# ECG-BioZ-Holter.net
KiCad netlist of a schematic drawn in EAGLE
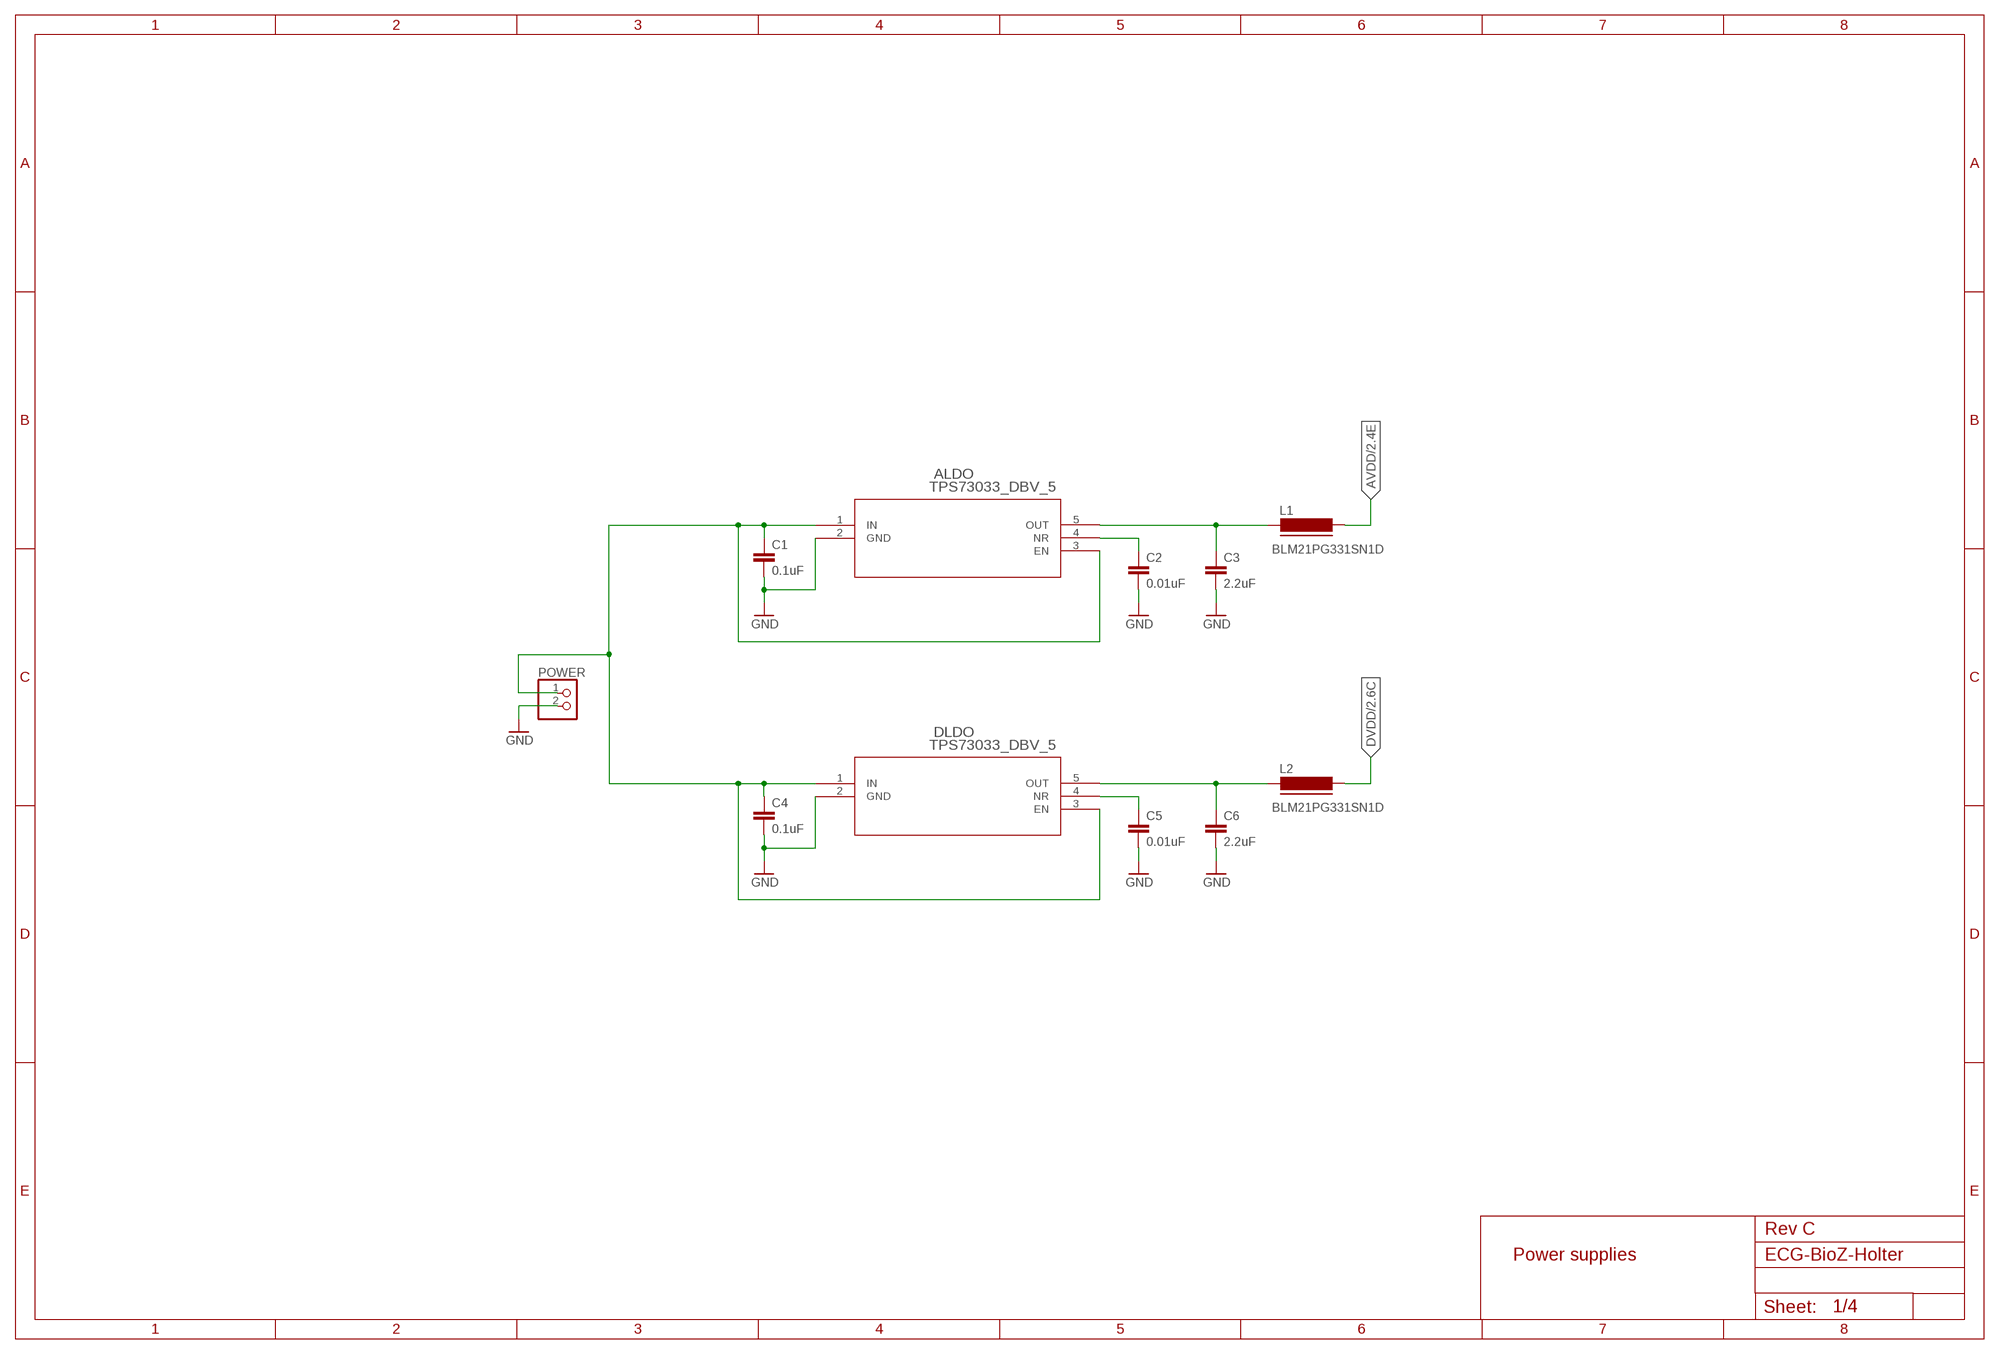
[diagram p0: schematic, sheet 1]
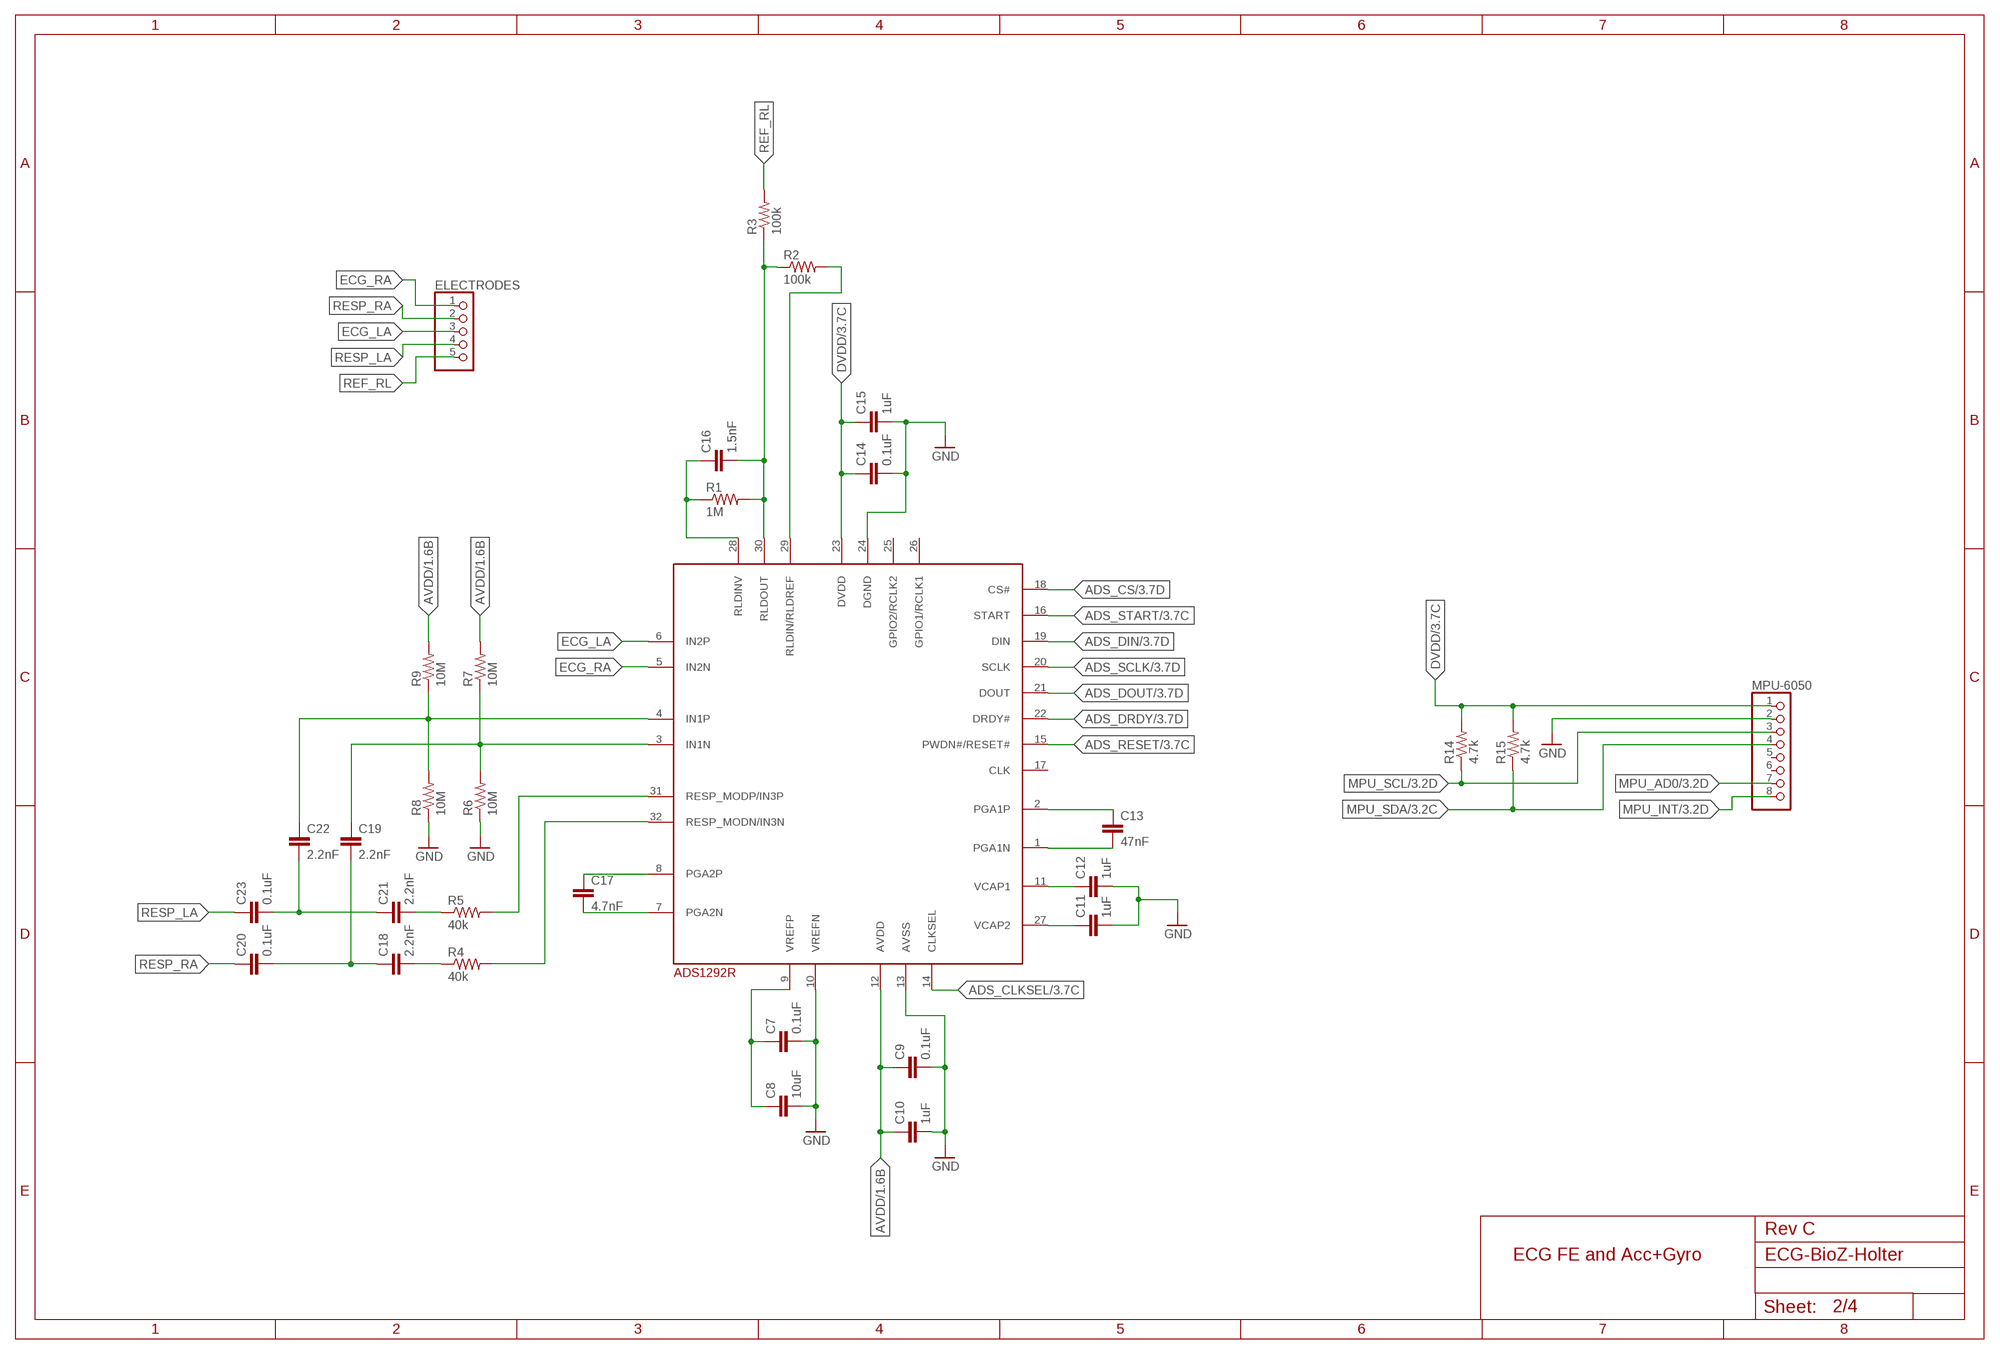
[diagram p1: schematic, sheet 2]
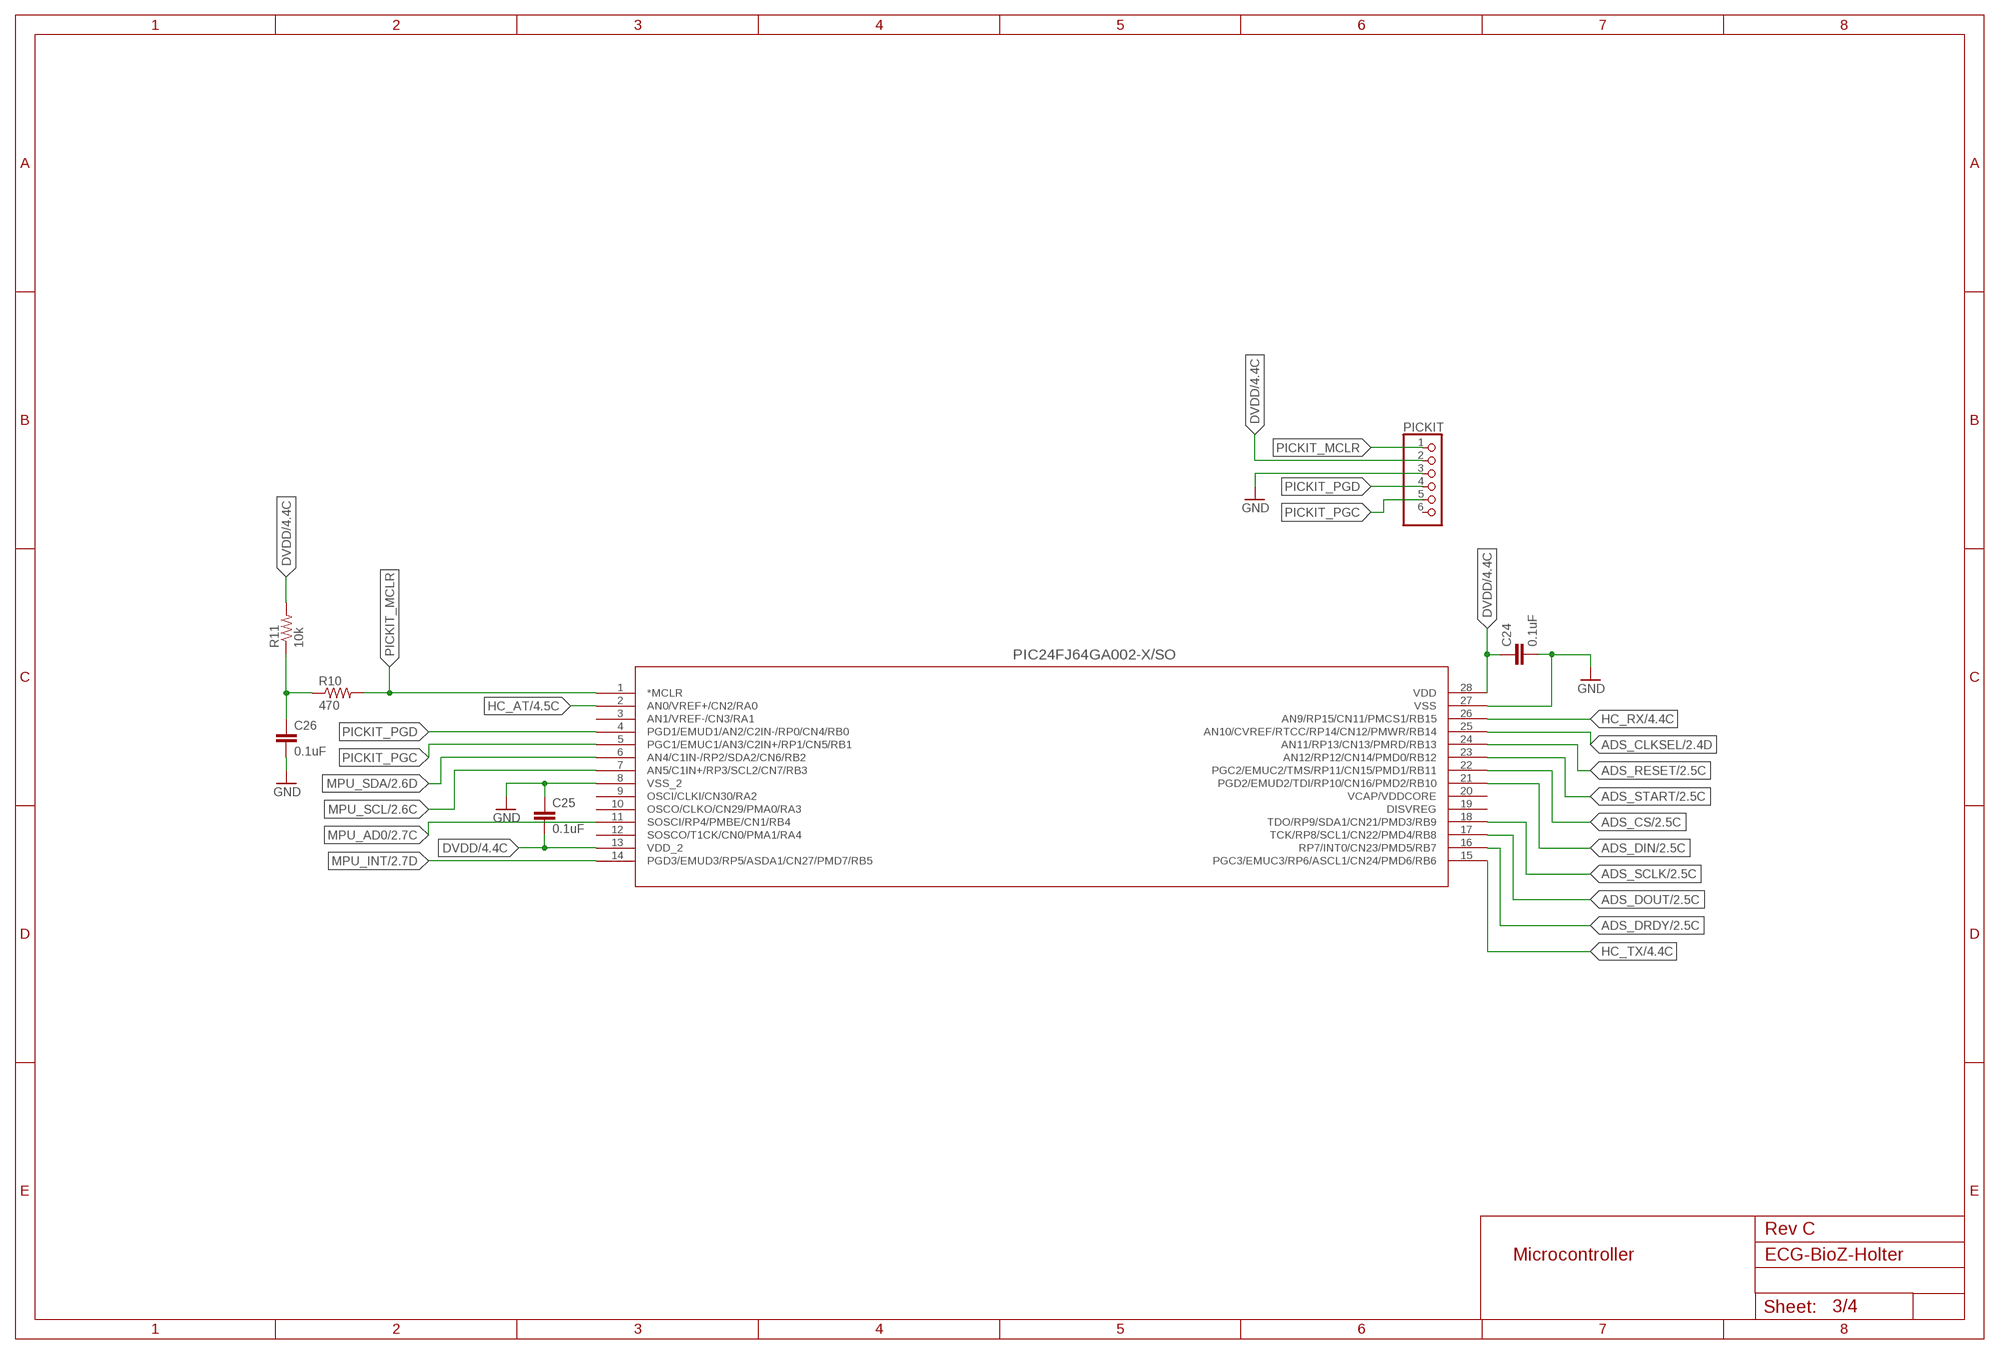
[diagram p2: schematic, sheet 3]
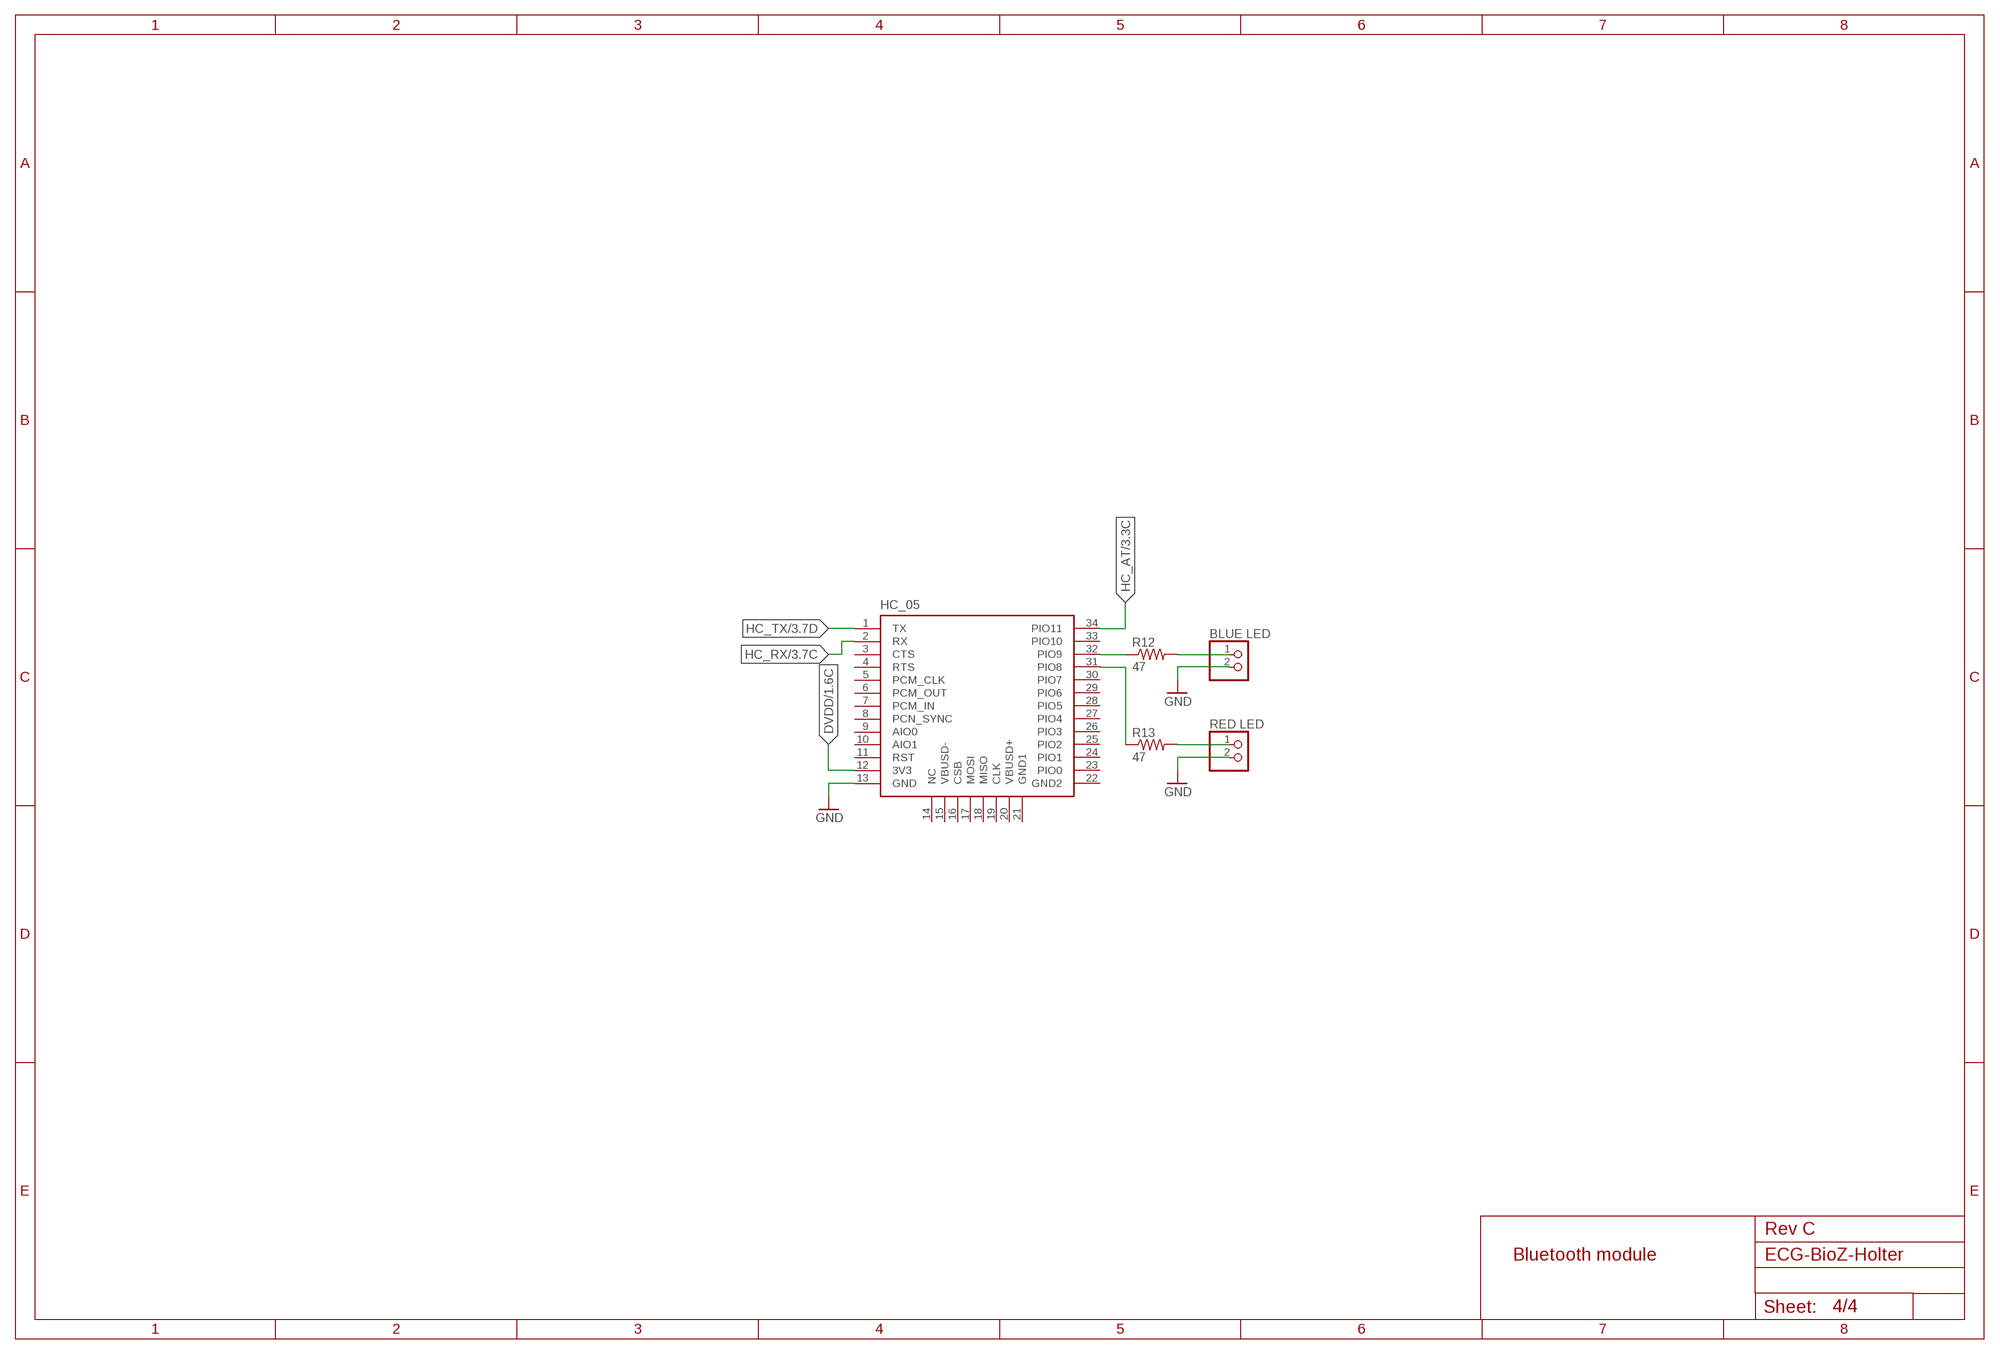
[diagram p3: schematic, sheet 4]

(export (version "E")
  (design (tool "Eeschema 10.0.6"))
  (components
    (comp (ref "ALDO")
      (value "TPS73033_DBV_5")
      (footprint "eagle-import:DBV5")
      (fields
        (field (name "GENERIC_PART_NUMBER") "TPS73033")
        (field (name "MANUFACTURER") "Texas Instruments")
        (field (name "MANUFACTURER_PART_NUMBER") "tps73033_dbv_5")
      )
      (libsource (lib "eagle-import") (part "TPS73033_DBV_5"))
    )
    (comp (ref "C1")
      (value "0.1uF")
      (footprint "eagle-import:C0805")
      (libsource (lib "eagle-import") (part "C-EUC0805"))
    )
    (comp (ref "C2")
      (value "0.01uF")
      (footprint "eagle-import:C0805")
      (libsource (lib "eagle-import") (part "C-EUC0805"))
    )
    (comp (ref "C3")
      (value "2.2uF")
      (footprint "eagle-import:C0805")
      (libsource (lib "eagle-import") (part "C-EUC0805"))
    )
    (comp (ref "C4")
      (value "0.1uF")
      (footprint "eagle-import:C0805")
      (libsource (lib "eagle-import") (part "C-EUC0805"))
    )
    (comp (ref "C5")
      (value "0.01uF")
      (footprint "eagle-import:C0805")
      (libsource (lib "eagle-import") (part "C-EUC0805"))
    )
    (comp (ref "C6")
      (value "2.2uF")
      (footprint "eagle-import:C0805")
      (libsource (lib "eagle-import") (part "C-EUC0805"))
    )
    (comp (ref "DLDO")
      (value "TPS73033_DBV_5")
      (footprint "eagle-import:DBV5")
      (fields
        (field (name "GENERIC_PART_NUMBER") "TPS73033")
        (field (name "MANUFACTURER") "Texas Instruments")
        (field (name "MANUFACTURER_PART_NUMBER") "tps73033_dbv_5")
      )
      (libsource (lib "eagle-import") (part "TPS73033_DBV_5"))
    )
    (comp (ref "L1")
      (value "BLM21PG331SN1D")
      (footprint "eagle-import:FB805")
      (libsource (lib "eagle-import") (part "FERRITE-0805"))
    )
    (comp (ref "L2")
      (value "BLM21PG331SN1D")
      (footprint "eagle-import:FB805")
      (libsource (lib "eagle-import") (part "FERRITE-0805"))
    )
    (comp (ref "POWER")
      (value "PINHD-1X2")
      (footprint "eagle-import:1X02")
      (libsource (lib "eagle-import") (part "PINHD-1X2"))
    )
    (comp (ref "C24")
      (value "0.1uF")
      (footprint "eagle-import:C0805")
      (libsource (lib "eagle-import") (part "C-EUC0805"))
    )
    (comp (ref "C25")
      (value "0.1uF")
      (footprint "eagle-import:C0805")
      (libsource (lib "eagle-import") (part "C-EUC0805"))
    )
    (comp (ref "C26")
      (value "0.1uF")
      (footprint "eagle-import:C0805")
      (libsource (lib "eagle-import") (part "C-EUC0805"))
    )
    (comp (ref "PIC24F")
      (value "PIC24FJ64GA002-X/SO")
      (footprint "eagle-import:SOIC28-W_MC")
      (libsource (lib "eagle-import") (part "PIC24FJ64GA002-X/SO"))
    )
    (comp (ref "PICKIT")
      (value "PINHD-1X6")
      (footprint "eagle-import:1X06")
      (libsource (lib "eagle-import") (part "PINHD-1X6"))
    )
    (comp (ref "R10")
      (value "470")
      (footprint "eagle-import:R0805")
      (libsource (lib "eagle-import") (part "R-US_R0805"))
    )
    (comp (ref "R11")
      (value "10k")
      (footprint "eagle-import:R0805")
      (libsource (lib "eagle-import") (part "R-US_R0805"))
    )
    (comp (ref "ADS1292R")
      (value "ADS1292R")
      (footprint "eagle-import:TQFP-32")
      (libsource (lib "eagle-import") (part "ADS1292R"))
    )
    (comp (ref "C7")
      (value "0.1uF")
      (footprint "eagle-import:C0805")
      (libsource (lib "eagle-import") (part "C-EUC0805"))
    )
    (comp (ref "C8")
      (value "10uF")
      (footprint "eagle-import:C0805")
      (libsource (lib "eagle-import") (part "C-EUC0805"))
    )
    (comp (ref "C9")
      (value "0.1uF")
      (footprint "eagle-import:C0805")
      (libsource (lib "eagle-import") (part "C-EUC0805"))
    )
    (comp (ref "C10")
      (value "1uF")
      (footprint "eagle-import:C0805")
      (libsource (lib "eagle-import") (part "C-EUC0805"))
    )
    (comp (ref "C11")
      (value "1uF")
      (footprint "eagle-import:C0805")
      (libsource (lib "eagle-import") (part "C-EUC0805"))
    )
    (comp (ref "C12")
      (value "1uF")
      (footprint "eagle-import:C0805")
      (libsource (lib "eagle-import") (part "C-EUC0805"))
    )
    (comp (ref "C13")
      (value "47nF")
      (footprint "eagle-import:C0805")
      (libsource (lib "eagle-import") (part "C-EUC0805"))
    )
    (comp (ref "C14")
      (value "0.1uF")
      (footprint "eagle-import:C0805")
      (libsource (lib "eagle-import") (part "C-EUC0805"))
    )
    (comp (ref "C15")
      (value "1uF")
      (footprint "eagle-import:C0805")
      (libsource (lib "eagle-import") (part "C-EUC0805"))
    )
    (comp (ref "C16")
      (value "1.5nF")
      (footprint "eagle-import:C0805")
      (libsource (lib "eagle-import") (part "C-EUC0805"))
    )
    (comp (ref "C17")
      (value "4.7nF")
      (footprint "eagle-import:C0805")
      (libsource (lib "eagle-import") (part "C-EUC0805"))
    )
    (comp (ref "C18")
      (value "2.2nF")
      (footprint "eagle-import:C0805")
      (libsource (lib "eagle-import") (part "C-EUC0805"))
    )
    (comp (ref "C19")
      (value "2.2nF")
      (footprint "eagle-import:C0805")
      (libsource (lib "eagle-import") (part "C-EUC0805"))
    )
    (comp (ref "C20")
      (value "0.1uF")
      (footprint "eagle-import:C0805")
      (libsource (lib "eagle-import") (part "C-EUC0805"))
    )
    (comp (ref "C21")
      (value "2.2nF")
      (footprint "eagle-import:C0805")
      (libsource (lib "eagle-import") (part "C-EUC0805"))
    )
    (comp (ref "C22")
      (value "2.2nF")
      (footprint "eagle-import:C0805")
      (libsource (lib "eagle-import") (part "C-EUC0805"))
    )
    (comp (ref "C23")
      (value "0.1uF")
      (footprint "eagle-import:C0805")
      (libsource (lib "eagle-import") (part "C-EUC0805"))
    )
    (comp (ref "ELECTRODES")
      (value "PINHD-1X5")
      (footprint "eagle-import:1X05")
      (libsource (lib "eagle-import") (part "PINHD-1X5"))
    )
    (comp (ref "MPU")
      (value "MPU-6050")
      (footprint "eagle-import:1X08")
      (libsource (lib "eagle-import") (part "PINHD-1X8"))
    )
    (comp (ref "R1")
      (value "1M")
      (footprint "eagle-import:R0805")
      (libsource (lib "eagle-import") (part "R-US_R0805"))
    )
    (comp (ref "R2")
      (value "100k")
      (footprint "eagle-import:R0805")
      (libsource (lib "eagle-import") (part "R-US_R0805"))
    )
    (comp (ref "R3")
      (value "100k")
      (footprint "eagle-import:R0805")
      (libsource (lib "eagle-import") (part "R-US_R0805"))
    )
    (comp (ref "R4")
      (value "40k")
      (footprint "eagle-import:R0805")
      (libsource (lib "eagle-import") (part "R-US_R0805"))
    )
    (comp (ref "R5")
      (value "40k")
      (footprint "eagle-import:R0805")
      (libsource (lib "eagle-import") (part "R-US_R0805"))
    )
    (comp (ref "R6")
      (value "10M")
      (footprint "eagle-import:R0805")
      (libsource (lib "eagle-import") (part "R-US_R0805"))
    )
    (comp (ref "R7")
      (value "10M")
      (footprint "eagle-import:R0805")
      (libsource (lib "eagle-import") (part "R-US_R0805"))
    )
    (comp (ref "R8")
      (value "10M")
      (footprint "eagle-import:R0805")
      (libsource (lib "eagle-import") (part "R-US_R0805"))
    )
    (comp (ref "R9")
      (value "10M")
      (footprint "eagle-import:R0805")
      (libsource (lib "eagle-import") (part "R-US_R0805"))
    )
    (comp (ref "R14")
      (value "4.7k")
      (footprint "eagle-import:R0805")
      (libsource (lib "eagle-import") (part "R-US_R0805"))
    )
    (comp (ref "R15")
      (value "4.7k")
      (footprint "eagle-import:R0805")
      (libsource (lib "eagle-import") (part "R-US_R0805"))
    )
    (comp (ref "BLUE")
      (value "BLUE LED")
      (footprint "eagle-import:1X02")
      (libsource (lib "eagle-import") (part "PINHD-1X2"))
    )
    (comp (ref "HC_05")
      (value "HC_05")
      (footprint "eagle-import:BLUETOOTH_SMD")
      (libsource (lib "eagle-import") (part "HC_05"))
    )
    (comp (ref "R12")
      (value "47")
      (footprint "eagle-import:R0805")
      (libsource (lib "eagle-import") (part "R-US_R0805"))
    )
    (comp (ref "R13")
      (value "47")
      (footprint "eagle-import:R0805")
      (libsource (lib "eagle-import") (part "R-US_R0805"))
    )
    (comp (ref "RED")
      (value "RED LED")
      (footprint "eagle-import:1X02")
      (libsource (lib "eagle-import") (part "PINHD-1X2"))
    )
  )
  (nets
    (net (code "1") (name "ADS_CLKSEL") (class "Default")
      (node (ref "ADS1292R") (pin "14") (pinfunction "CLKSEL_14") (pintype "bidirectional"))
      (node (ref "PIC24F") (pin "25") (pinfunction "AN10/CVREF/RTCC/RP14/CN12/PMWR/RB14_25") (pintype "passive"))
    )
    (net (code "2") (name "ADS_CS") (class "Default")
      (node (ref "ADS1292R") (pin "18") (pinfunction "CS#_18") (pintype "bidirectional"))
      (node (ref "PIC24F") (pin "22") (pinfunction "PGC2/EMUC2/TMS/RP11/CN15/PMD1/RB11_22") (pintype "passive"))
    )
    (net (code "3") (name "ADS_DIN") (class "Default")
      (node (ref "ADS1292R") (pin "19") (pinfunction "DIN_19") (pintype "bidirectional"))
      (node (ref "PIC24F") (pin "21") (pinfunction "PGD2/EMUD2/TDI/RP10/CN16/PMD2/RB10_21") (pintype "passive"))
    )
    (net (code "4") (name "ADS_DOUT") (class "Default")
      (node (ref "ADS1292R") (pin "21") (pinfunction "DOUT_21") (pintype "bidirectional"))
      (node (ref "PIC24F") (pin "17") (pinfunction "TCK/RP8/SCL1/CN22/PMD4/RB8_17") (pintype "passive"))
    )
    (net (code "5") (name "ADS_DRDY") (class "Default")
      (node (ref "ADS1292R") (pin "22") (pinfunction "DRDY#_22") (pintype "bidirectional"))
      (node (ref "PIC24F") (pin "16") (pinfunction "RP7/INT0/CN23/PMD5/RB7_16") (pintype "passive"))
    )
    (net (code "6") (name "ADS_RESET") (class "Default")
      (node (ref "ADS1292R") (pin "15") (pinfunction "PWDN#/RESET#_15") (pintype "bidirectional"))
      (node (ref "PIC24F") (pin "24") (pinfunction "AN11/RP13/CN13/PMRD/RB13_24") (pintype "passive"))
    )
    (net (code "7") (name "ADS_SCLK") (class "Default")
      (node (ref "ADS1292R") (pin "20") (pinfunction "SCLK_20") (pintype "bidirectional"))
      (node (ref "PIC24F") (pin "18") (pinfunction "TDO/RP9/SDA1/CN21/PMD3/RB9_18") (pintype "passive"))
    )
    (net (code "8") (name "ADS_START") (class "Default")
      (node (ref "ADS1292R") (pin "16") (pinfunction "START_16") (pintype "bidirectional"))
      (node (ref "PIC24F") (pin "23") (pinfunction "AN12/RP12/CN14/PMD0/RB12_23") (pintype "passive"))
    )
    (net (code "9") (name "AVDD") (class "Default")
      (node (ref "ADS1292R") (pin "12") (pinfunction "AVDD_12") (pintype "bidirectional"))
      (node (ref "C10") (pin "1") (pinfunction "1_1") (pintype "passive"))
      (node (ref "C9") (pin "1") (pinfunction "1_1") (pintype "passive"))
      (node (ref "L1") (pin "2") (pinfunction "2_2") (pintype "passive"))
      (node (ref "R7") (pin "2") (pinfunction "2_2") (pintype "passive"))
      (node (ref "R9") (pin "2") (pinfunction "2_2") (pintype "passive"))
    )
    (net (code "10") (name "DVDD") (class "Default")
      (node (ref "ADS1292R") (pin "23") (pinfunction "DVDD_23") (pintype "bidirectional"))
      (node (ref "C14") (pin "1") (pinfunction "1_1") (pintype "passive"))
      (node (ref "C15") (pin "1") (pinfunction "1_1") (pintype "passive"))
      (node (ref "C24") (pin "1") (pinfunction "1_1") (pintype "passive"))
      (node (ref "C25") (pin "2") (pinfunction "2_2") (pintype "passive"))
      (node (ref "HC_05") (pin "12") (pinfunction "3V3_12") (pintype "bidirectional"))
      (node (ref "L2") (pin "2") (pinfunction "2_2") (pintype "passive"))
      (node (ref "MPU") (pin "1") (pinfunction "1_1") (pintype "passive"))
      (node (ref "PIC24F") (pin "13") (pinfunction "VDD_2_13") (pintype "passive"))
      (node (ref "PIC24F") (pin "28") (pinfunction "VDD_28") (pintype "passive"))
      (node (ref "PICKIT") (pin "2") (pinfunction "2_2") (pintype "passive"))
      (node (ref "R11") (pin "2") (pinfunction "2_2") (pintype "passive"))
      (node (ref "R14") (pin "2") (pinfunction "2_2") (pintype "passive"))
      (node (ref "R15") (pin "2") (pinfunction "2_2") (pintype "passive"))
    )
    (net (code "11") (name "ECG_LA") (class "Default")
      (node (ref "ADS1292R") (pin "6") (pinfunction "IN2P_6") (pintype "bidirectional"))
      (node (ref "ELECTRODES") (pin "3") (pinfunction "3_3") (pintype "passive"))
    )
    (net (code "12") (name "ECG_RA") (class "Default")
      (node (ref "ADS1292R") (pin "5") (pinfunction "IN2N_5") (pintype "bidirectional"))
      (node (ref "ELECTRODES") (pin "1") (pinfunction "1_1") (pintype "passive"))
    )
    (net (code "13") (name "GND") (class "Default")
      (node (ref "ADS1292R") (pin "10") (pinfunction "VREFN_10") (pintype "bidirectional"))
      (node (ref "ADS1292R") (pin "13") (pinfunction "AVSS_13") (pintype "bidirectional"))
      (node (ref "ADS1292R") (pin "24") (pinfunction "DGND_24") (pintype "bidirectional"))
      (node (ref "ALDO") (pin "2") (pinfunction "GND_2") (pintype "power_in"))
      (node (ref "BLUE") (pin "2") (pinfunction "2_2") (pintype "passive"))
      (node (ref "C1") (pin "2") (pinfunction "2_2") (pintype "passive"))
      (node (ref "C10") (pin "2") (pinfunction "2_2") (pintype "passive"))
      (node (ref "C11") (pin "2") (pinfunction "2_2") (pintype "passive"))
      (node (ref "C12") (pin "2") (pinfunction "2_2") (pintype "passive"))
      (node (ref "C14") (pin "2") (pinfunction "2_2") (pintype "passive"))
      (node (ref "C15") (pin "2") (pinfunction "2_2") (pintype "passive"))
      (node (ref "C2") (pin "2") (pinfunction "2_2") (pintype "passive"))
      (node (ref "C24") (pin "2") (pinfunction "2_2") (pintype "passive"))
      (node (ref "C25") (pin "1") (pinfunction "1_1") (pintype "passive"))
      (node (ref "C26") (pin "2") (pinfunction "2_2") (pintype "passive"))
      (node (ref "C3") (pin "2") (pinfunction "2_2") (pintype "passive"))
      (node (ref "C4") (pin "2") (pinfunction "2_2") (pintype "passive"))
      (node (ref "C5") (pin "2") (pinfunction "2_2") (pintype "passive"))
      (node (ref "C6") (pin "2") (pinfunction "2_2") (pintype "passive"))
      (node (ref "C7") (pin "2") (pinfunction "2_2") (pintype "passive"))
      (node (ref "C8") (pin "2") (pinfunction "2_2") (pintype "passive"))
      (node (ref "C9") (pin "2") (pinfunction "2_2") (pintype "passive"))
      (node (ref "DLDO") (pin "2") (pinfunction "GND_2") (pintype "power_in"))
      (node (ref "HC_05") (pin "13") (pinfunction "GND_13") (pintype "bidirectional"))
      (node (ref "MPU") (pin "2") (pinfunction "2_2") (pintype "passive"))
      (node (ref "PIC24F") (pin "27") (pinfunction "VSS_27") (pintype "passive"))
      (node (ref "PIC24F") (pin "8") (pinfunction "VSS_2_8") (pintype "passive"))
      (node (ref "PICKIT") (pin "3") (pinfunction "3_3") (pintype "passive"))
      (node (ref "POWER") (pin "2") (pinfunction "2_2") (pintype "passive"))
      (node (ref "R6") (pin "1") (pinfunction "1_1") (pintype "passive"))
      (node (ref "R8") (pin "1") (pinfunction "1_1") (pintype "passive"))
      (node (ref "RED") (pin "2") (pinfunction "2_2") (pintype "passive"))
    )
    (net (code "14") (name "HC_AT") (class "Default")
      (node (ref "HC_05") (pin "34") (pinfunction "PIO11_34") (pintype "bidirectional"))
      (node (ref "PIC24F") (pin "2") (pinfunction "AN0/VREF+/CN2/RA0_2") (pintype "passive"))
    )
    (net (code "15") (name "HC_RX") (class "Default")
      (node (ref "HC_05") (pin "2") (pinfunction "RX_2") (pintype "bidirectional"))
      (node (ref "PIC24F") (pin "26") (pinfunction "AN9/RP15/CN11/PMCS1/RB15_26") (pintype "passive"))
    )
    (net (code "16") (name "HC_TX") (class "Default")
      (node (ref "HC_05") (pin "1") (pinfunction "TX_1") (pintype "bidirectional"))
      (node (ref "PIC24F") (pin "15") (pinfunction "PGC3/EMUC3/RP6/ASCL1/CN24/PMD6/RB6_15") (pintype "passive"))
    )
    (net (code "17") (name "MPU_AD0") (class "Default")
      (node (ref "MPU") (pin "7") (pinfunction "7_7") (pintype "passive"))
      (node (ref "PIC24F") (pin "11") (pinfunction "SOSCI/RP4/PMBE/CN1/RB4_11") (pintype "passive"))
    )
    (net (code "18") (name "MPU_INT") (class "Default")
      (node (ref "MPU") (pin "8") (pinfunction "8_8") (pintype "passive"))
      (node (ref "PIC24F") (pin "14") (pinfunction "PGD3/EMUD3/RP5/ASDA1/CN27/PMD7/RB5_14") (pintype "passive"))
    )
    (net (code "19") (name "MPU_SCL") (class "Default")
      (node (ref "MPU") (pin "3") (pinfunction "3_3") (pintype "passive"))
      (node (ref "PIC24F") (pin "7") (pinfunction "AN5/C1IN+/RP3/SCL2/CN7/RB3_7") (pintype "passive"))
      (node (ref "R14") (pin "1") (pinfunction "1_1") (pintype "passive"))
    )
    (net (code "20") (name "MPU_SDA") (class "Default")
      (node (ref "MPU") (pin "4") (pinfunction "4_4") (pintype "passive"))
      (node (ref "PIC24F") (pin "6") (pinfunction "AN4/C1IN-/RP2/SDA2/CN6/RB2_6") (pintype "passive"))
      (node (ref "R15") (pin "1") (pinfunction "1_1") (pintype "passive"))
    )
    (net (code "21") (name "Net-(ADS1292R-IN1N)") (class "Default")
      (node (ref "ADS1292R") (pin "3") (pinfunction "IN1N_3") (pintype "bidirectional"))
      (node (ref "C19") (pin "1") (pinfunction "1_1") (pintype "passive"))
      (node (ref "R6") (pin "2") (pinfunction "2_2") (pintype "passive"))
      (node (ref "R7") (pin "1") (pinfunction "1_1") (pintype "passive"))
    )
    (net (code "22") (name "Net-(ADS1292R-IN1P)") (class "Default")
      (node (ref "ADS1292R") (pin "4") (pinfunction "IN1P_4") (pintype "bidirectional"))
      (node (ref "C22") (pin "1") (pinfunction "1_1") (pintype "passive"))
      (node (ref "R8") (pin "2") (pinfunction "2_2") (pintype "passive"))
      (node (ref "R9") (pin "1") (pinfunction "1_1") (pintype "passive"))
    )
    (net (code "23") (name "Net-(ADS1292R-PGA1N)") (class "Default")
      (node (ref "ADS1292R") (pin "1") (pinfunction "PGA1N_1") (pintype "bidirectional"))
      (node (ref "C13") (pin "2") (pinfunction "2_2") (pintype "passive"))
    )
    (net (code "24") (name "Net-(ADS1292R-PGA1P)") (class "Default")
      (node (ref "ADS1292R") (pin "2") (pinfunction "PGA1P_2") (pintype "bidirectional"))
      (node (ref "C13") (pin "1") (pinfunction "1_1") (pintype "passive"))
    )
    (net (code "25") (name "Net-(ADS1292R-PGA2N)") (class "Default")
      (node (ref "ADS1292R") (pin "7") (pinfunction "PGA2N_7") (pintype "bidirectional"))
      (node (ref "C17") (pin "2") (pinfunction "2_2") (pintype "passive"))
    )
    (net (code "26") (name "Net-(ADS1292R-PGA2P)") (class "Default")
      (node (ref "ADS1292R") (pin "8") (pinfunction "PGA2P_8") (pintype "bidirectional"))
      (node (ref "C17") (pin "1") (pinfunction "1_1") (pintype "passive"))
    )
    (net (code "27") (name "Net-(ADS1292R-RESP_MODN{slash}IN3N)") (class "Default")
      (node (ref "ADS1292R") (pin "32") (pinfunction "RESP_MODN/IN3N_32") (pintype "bidirectional"))
      (node (ref "R4") (pin "2") (pinfunction "2_2") (pintype "passive"))
    )
    (net (code "28") (name "Net-(ADS1292R-RESP_MODP{slash}IN3P)") (class "Default")
      (node (ref "ADS1292R") (pin "31") (pinfunction "RESP_MODP/IN3P_31") (pintype "bidirectional"))
      (node (ref "R5") (pin "2") (pinfunction "2_2") (pintype "passive"))
    )
    (net (code "29") (name "Net-(ADS1292R-RLDINV)") (class "Default")
      (node (ref "ADS1292R") (pin "28") (pinfunction "RLDINV_28") (pintype "bidirectional"))
      (node (ref "C16") (pin "1") (pinfunction "1_1") (pintype "passive"))
      (node (ref "R1") (pin "1") (pinfunction "1_1") (pintype "passive"))
    )
    (net (code "30") (name "Net-(ADS1292R-RLDIN{slash}RLDREF)") (class "Default")
      (node (ref "ADS1292R") (pin "29") (pinfunction "RLDIN/RLDREF_29") (pintype "bidirectional"))
      (node (ref "R2") (pin "2") (pinfunction "2_2") (pintype "passive"))
    )
    (net (code "31") (name "Net-(ADS1292R-RLDOUT)") (class "Default")
      (node (ref "ADS1292R") (pin "30") (pinfunction "RLDOUT_30") (pintype "bidirectional"))
      (node (ref "C16") (pin "2") (pinfunction "2_2") (pintype "passive"))
      (node (ref "R1") (pin "2") (pinfunction "2_2") (pintype "passive"))
      (node (ref "R2") (pin "1") (pinfunction "1_1") (pintype "passive"))
      (node (ref "R3") (pin "1") (pinfunction "1_1") (pintype "passive"))
    )
    (net (code "32") (name "Net-(ADS1292R-VCAP1)") (class "Default")
      (node (ref "ADS1292R") (pin "11") (pinfunction "VCAP1_11") (pintype "bidirectional"))
      (node (ref "C12") (pin "1") (pinfunction "1_1") (pintype "passive"))
    )
    (net (code "33") (name "Net-(ADS1292R-VCAP2)") (class "Default")
      (node (ref "ADS1292R") (pin "27") (pinfunction "VCAP2_27") (pintype "bidirectional"))
      (node (ref "C11") (pin "1") (pinfunction "1_1") (pintype "passive"))
    )
    (net (code "34") (name "Net-(ADS1292R-VREFP)") (class "Default")
      (node (ref "ADS1292R") (pin "9") (pinfunction "VREFP_9") (pintype "bidirectional"))
      (node (ref "C7") (pin "1") (pinfunction "1_1") (pintype "passive"))
      (node (ref "C8") (pin "1") (pinfunction "1_1") (pintype "passive"))
    )
    (net (code "35") (name "Net-(ALDO-EN)") (class "Default")
      (node (ref "ALDO") (pin "1") (pinfunction "IN_1") (pintype "input"))
      (node (ref "ALDO") (pin "3") (pinfunction "EN_3") (pintype "passive"))
      (node (ref "C1") (pin "1") (pinfunction "1_1") (pintype "passive"))
      (node (ref "C4") (pin "1") (pinfunction "1_1") (pintype "passive"))
      (node (ref "DLDO") (pin "1") (pinfunction "IN_1") (pintype "input"))
      (node (ref "DLDO") (pin "3") (pinfunction "EN_3") (pintype "passive"))
      (node (ref "POWER") (pin "1") (pinfunction "1_1") (pintype "passive"))
    )
    (net (code "36") (name "Net-(ALDO-NR)") (class "Default")
      (node (ref "ALDO") (pin "4") (pinfunction "NR_4") (pintype "passive"))
      (node (ref "C2") (pin "1") (pinfunction "1_1") (pintype "passive"))
    )
    (net (code "37") (name "Net-(ALDO-OUT)") (class "Default")
      (node (ref "ALDO") (pin "5") (pinfunction "OUT_5") (pintype "output"))
      (node (ref "C3") (pin "1") (pinfunction "1_1") (pintype "passive"))
      (node (ref "L1") (pin "1") (pinfunction "1_1") (pintype "passive"))
    )
    (net (code "38") (name "Net-(BLUE-Pad1)") (class "Default")
      (node (ref "BLUE") (pin "1") (pinfunction "1_1") (pintype "passive"))
      (node (ref "R12") (pin "2") (pinfunction "2_2") (pintype "passive"))
    )
    (net (code "39") (name "Net-(C18-Pad1)") (class "Default")
      (node (ref "C18") (pin "1") (pinfunction "1_1") (pintype "passive"))
      (node (ref "C19") (pin "2") (pinfunction "2_2") (pintype "passive"))
      (node (ref "C20") (pin "2") (pinfunction "2_2") (pintype "passive"))
    )
    (net (code "40") (name "Net-(C18-Pad2)") (class "Default")
      (node (ref "C18") (pin "2") (pinfunction "2_2") (pintype "passive"))
      (node (ref "R4") (pin "1") (pinfunction "1_1") (pintype "passive"))
    )
    (net (code "41") (name "Net-(C21-Pad1)") (class "Default")
      (node (ref "C21") (pin "1") (pinfunction "1_1") (pintype "passive"))
      (node (ref "C22") (pin "2") (pinfunction "2_2") (pintype "passive"))
      (node (ref "C23") (pin "2") (pinfunction "2_2") (pintype "passive"))
    )
    (net (code "42") (name "Net-(C21-Pad2)") (class "Default")
      (node (ref "C21") (pin "2") (pinfunction "2_2") (pintype "passive"))
      (node (ref "R5") (pin "1") (pinfunction "1_1") (pintype "passive"))
    )
    (net (code "43") (name "Net-(C26-Pad1)") (class "Default")
      (node (ref "C26") (pin "1") (pinfunction "1_1") (pintype "passive"))
      (node (ref "R10") (pin "1") (pinfunction "1_1") (pintype "passive"))
      (node (ref "R11") (pin "1") (pinfunction "1_1") (pintype "passive"))
    )
    (net (code "44") (name "Net-(DLDO-NR)") (class "Default")
      (node (ref "C5") (pin "1") (pinfunction "1_1") (pintype "passive"))
      (node (ref "DLDO") (pin "4") (pinfunction "NR_4") (pintype "passive"))
    )
    (net (code "45") (name "Net-(DLDO-OUT)") (class "Default")
      (node (ref "C6") (pin "1") (pinfunction "1_1") (pintype "passive"))
      (node (ref "DLDO") (pin "5") (pinfunction "OUT_5") (pintype "output"))
      (node (ref "L2") (pin "1") (pinfunction "1_1") (pintype "passive"))
    )
    (net (code "46") (name "Net-(HC_05-PIO8)") (class "Default")
      (node (ref "HC_05") (pin "31") (pinfunction "PIO8_31") (pintype "bidirectional"))
      (node (ref "R13") (pin "1") (pinfunction "1_1") (pintype "passive"))
    )
    (net (code "47") (name "Net-(HC_05-PIO9)") (class "Default")
      (node (ref "HC_05") (pin "32") (pinfunction "PIO9_32") (pintype "bidirectional"))
      (node (ref "R12") (pin "1") (pinfunction "1_1") (pintype "passive"))
    )
    (net (code "48") (name "Net-(R13-Pad2)") (class "Default")
      (node (ref "R13") (pin "2") (pinfunction "2_2") (pintype "passive"))
      (node (ref "RED") (pin "1") (pinfunction "1_1") (pintype "passive"))
    )
    (net (code "49") (name "PICKIT_MCLR") (class "Default")
      (node (ref "PIC24F") (pin "1") (pinfunction "*MCLR_1") (pintype "passive"))
      (node (ref "PICKIT") (pin "1") (pinfunction "1_1") (pintype "passive"))
      (node (ref "R10") (pin "2") (pinfunction "2_2") (pintype "passive"))
    )
    (net (code "50") (name "PICKIT_PGC") (class "Default")
      (node (ref "PIC24F") (pin "5") (pinfunction "PGC1/EMUC1/AN3/C2IN+/RP1/CN5/RB1_5") (pintype "passive"))
      (node (ref "PICKIT") (pin "5") (pinfunction "5_5") (pintype "passive"))
    )
    (net (code "51") (name "PICKIT_PGD") (class "Default")
      (node (ref "PIC24F") (pin "4") (pinfunction "PGD1/EMUD1/AN2/C2IN-/RP0/CN4/RB0_4") (pintype "passive"))
      (node (ref "PICKIT") (pin "4") (pinfunction "4_4") (pintype "passive"))
    )
    (net (code "52") (name "REF_RL") (class "Default")
      (node (ref "ELECTRODES") (pin "5") (pinfunction "5_5") (pintype "passive"))
      (node (ref "R3") (pin "2") (pinfunction "2_2") (pintype "passive"))
    )
    (net (code "53") (name "RESP_LA") (class "Default")
      (node (ref "C23") (pin "1") (pinfunction "1_1") (pintype "passive"))
      (node (ref "ELECTRODES") (pin "4") (pinfunction "4_4") (pintype "passive"))
    )
    (net (code "54") (name "RESP_RA") (class "Default")
      (node (ref "C20") (pin "1") (pinfunction "1_1") (pintype "passive"))
      (node (ref "ELECTRODES") (pin "2") (pinfunction "2_2") (pintype "passive"))
    )
    (net (code "55") (name "unconnected-(ADS1292R-CLK-Pad17)") (class "Default")
      (node (ref "ADS1292R") (pin "17") (pinfunction "CLK_17") (pintype "bidirectional"))
    )
    (net (code "56") (name "unconnected-(ADS1292R-GPIO1{slash}RCLK1-Pad26)") (class "Default")
      (node (ref "ADS1292R") (pin "26") (pinfunction "GPIO1/RCLK1_26") (pintype "bidirectional"))
    )
    (net (code "57") (name "unconnected-(ADS1292R-GPIO2{slash}RCLK2-Pad25)") (class "Default")
      (node (ref "ADS1292R") (pin "25") (pinfunction "GPIO2/RCLK2_25") (pintype "bidirectional"))
    )
    (net (code "58") (name "unconnected-(HC_05-AIO0-Pad9)") (class "Default")
      (node (ref "HC_05") (pin "9") (pinfunction "AIO0_9") (pintype "bidirectional"))
    )
    (net (code "59") (name "unconnected-(HC_05-AIO1-Pad10)") (class "Default")
      (node (ref "HC_05") (pin "10") (pinfunction "AIO1_10") (pintype "bidirectional"))
    )
    (net (code "60") (name "unconnected-(HC_05-CLK-Pad19)") (class "Default")
      (node (ref "HC_05") (pin "19") (pinfunction "CLK_19") (pintype "bidirectional"))
    )
    (net (code "61") (name "unconnected-(HC_05-CSB-Pad16)") (class "Default")
      (node (ref "HC_05") (pin "16") (pinfunction "CSB_16") (pintype "bidirectional"))
    )
    (net (code "62") (name "unconnected-(HC_05-CTS-Pad3)") (class "Default")
      (node (ref "HC_05") (pin "3") (pinfunction "CTS_3") (pintype "bidirectional"))
    )
    (net (code "63") (name "unconnected-(HC_05-GND1-Pad21)") (class "Default")
      (node (ref "HC_05") (pin "21") (pinfunction "GND1_21") (pintype "bidirectional"))
    )
    (net (code "64") (name "unconnected-(HC_05-GND2-Pad22)") (class "Default")
      (node (ref "HC_05") (pin "22") (pinfunction "GND2_22") (pintype "bidirectional"))
    )
    (net (code "65") (name "unconnected-(HC_05-MISO-Pad18)") (class "Default")
      (node (ref "HC_05") (pin "18") (pinfunction "MISO_18") (pintype "bidirectional"))
    )
    (net (code "66") (name "unconnected-(HC_05-MOSI-Pad17)") (class "Default")
      (node (ref "HC_05") (pin "17") (pinfunction "MOSI_17") (pintype "bidirectional"))
    )
    (net (code "67") (name "unconnected-(HC_05-NC-Pad14)") (class "Default")
      (node (ref "HC_05") (pin "14") (pinfunction "NC_14") (pintype "bidirectional"))
    )
    (net (code "68") (name "unconnected-(HC_05-PCM_CLK-Pad5)") (class "Default")
      (node (ref "HC_05") (pin "5") (pinfunction "PCM_CLK_5") (pintype "bidirectional"))
    )
    (net (code "69") (name "unconnected-(HC_05-PCM_IN-Pad7)") (class "Default")
      (node (ref "HC_05") (pin "7") (pinfunction "PCM_IN_7") (pintype "bidirectional"))
    )
    (net (code "70") (name "unconnected-(HC_05-PCM_OUT-Pad6)") (class "Default")
      (node (ref "HC_05") (pin "6") (pinfunction "PCM_OUT_6") (pintype "bidirectional"))
    )
    (net (code "71") (name "unconnected-(HC_05-PCN_SYNC-Pad8)") (class "Default")
      (node (ref "HC_05") (pin "8") (pinfunction "PCN_SYNC_8") (pintype "bidirectional"))
    )
    (net (code "72") (name "unconnected-(HC_05-PIO0-Pad23)") (class "Default")
      (node (ref "HC_05") (pin "23") (pinfunction "PIO0_23") (pintype "bidirectional"))
    )
    (net (code "73") (name "unconnected-(HC_05-PIO1-Pad24)") (class "Default")
      (node (ref "HC_05") (pin "24") (pinfunction "PIO1_24") (pintype "bidirectional"))
    )
    (net (code "74") (name "unconnected-(HC_05-PIO2-Pad25)") (class "Default")
      (node (ref "HC_05") (pin "25") (pinfunction "PIO2_25") (pintype "bidirectional"))
    )
    (net (code "75") (name "unconnected-(HC_05-PIO3-Pad26)") (class "Default")
      (node (ref "HC_05") (pin "26") (pinfunction "PIO3_26") (pintype "bidirectional"))
    )
    (net (code "76") (name "unconnected-(HC_05-PIO4-Pad27)") (class "Default")
      (node (ref "HC_05") (pin "27") (pinfunction "PIO4_27") (pintype "bidirectional"))
    )
    (net (code "77") (name "unconnected-(HC_05-PIO5-Pad28)") (class "Default")
      (node (ref "HC_05") (pin "28") (pinfunction "PIO5_28") (pintype "bidirectional"))
    )
    (net (code "78") (name "unconnected-(HC_05-PIO6-Pad29)") (class "Default")
      (node (ref "HC_05") (pin "29") (pinfunction "PIO6_29") (pintype "bidirectional"))
    )
    (net (code "79") (name "unconnected-(HC_05-PIO7-Pad30)") (class "Default")
      (node (ref "HC_05") (pin "30") (pinfunction "PIO7_30") (pintype "bidirectional"))
    )
    (net (code "80") (name "unconnected-(HC_05-PIO10-Pad33)") (class "Default")
      (node (ref "HC_05") (pin "33") (pinfunction "PIO10_33") (pintype "bidirectional"))
    )
    (net (code "81") (name "unconnected-(HC_05-RST-Pad11)") (class "Default")
      (node (ref "HC_05") (pin "11") (pinfunction "RST_11") (pintype "bidirectional"))
    )
    (net (code "82") (name "unconnected-(HC_05-RTS-Pad4)") (class "Default")
      (node (ref "HC_05") (pin "4") (pinfunction "RTS_4") (pintype "bidirectional"))
    )
    (net (code "83") (name "unconnected-(HC_05-VBUSD+-Pad20)") (class "Default")
      (node (ref "HC_05") (pin "20") (pinfunction "VBUSD+_20") (pintype "bidirectional"))
    )
    (net (code "84") (name "unconnected-(HC_05-VBUSD--Pad15)") (class "Default")
      (node (ref "HC_05") (pin "15") (pinfunction "VBUSD-_15") (pintype "bidirectional"))
    )
    (net (code "85") (name "unconnected-(MPU-Pad5)") (class "Default")
      (node (ref "MPU") (pin "5") (pinfunction "5_5") (pintype "passive"))
    )
    (net (code "86") (name "unconnected-(MPU-Pad6)") (class "Default")
      (node (ref "MPU") (pin "6") (pinfunction "6_6") (pintype "passive"))
    )
    (net (code "87") (name "unconnected-(PIC24F-AN1{slash}VREF-{slash}CN3{slash}RA1-Pad3)") (class "Default")
      (node (ref "PIC24F") (pin "3") (pinfunction "AN1/VREF-/CN3/RA1_3") (pintype "passive"))
    )
    (net (code "88") (name "unconnected-(PIC24F-DISVREG-Pad19)") (class "Default")
      (node (ref "PIC24F") (pin "19") (pinfunction "DISVREG_19") (pintype "passive"))
    )
    (net (code "89") (name "unconnected-(PIC24F-OSCI{slash}CLKI{slash}CN30{slash}RA2-Pad9)") (class "Default")
      (node (ref "PIC24F") (pin "9") (pinfunction "OSCI/CLKI/CN30/RA2_9") (pintype "passive"))
    )
    (net (code "90") (name "unconnected-(PIC24F-OSCO{slash}CLKO{slash}CN29{slash}PMA0{slash}RA3-Pad10)") (class "Default")
      (node (ref "PIC24F") (pin "10") (pinfunction "OSCO/CLKO/CN29/PMA0/RA3_10") (pintype "passive"))
    )
    (net (code "91") (name "unconnected-(PIC24F-SOSCO{slash}T1CK{slash}CN0{slash}PMA1{slash}RA4-Pad12)") (class "Default")
      (node (ref "PIC24F") (pin "12") (pinfunction "SOSCO/T1CK/CN0/PMA1/RA4_12") (pintype "passive"))
    )
    (net (code "92") (name "unconnected-(PIC24F-VCAP{slash}VDDCORE-Pad20)") (class "Default")
      (node (ref "PIC24F") (pin "20") (pinfunction "VCAP/VDDCORE_20") (pintype "passive"))
    )
    (net (code "93") (name "unconnected-(PICKIT-Pad6)") (class "Default")
      (node (ref "PICKIT") (pin "6") (pinfunction "6_6") (pintype "passive"))
    )
  )
)
